# ADC_Buffering.net
KiCad netlist of a schematic drawn in Altium Designer
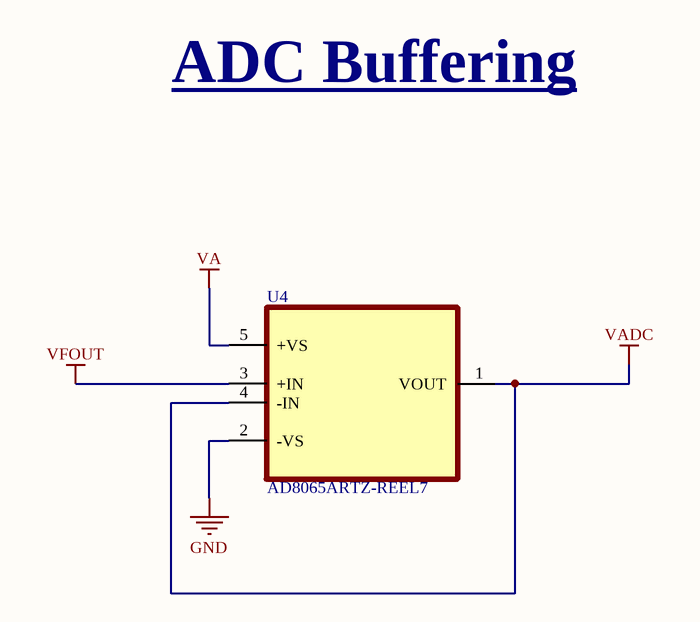
[diagram p0: ADC Buffering.SchDoc]

(export (version "E")
  (design (tool "Eeschema 10.0.6"))
  (components
    (comp (ref "U4")
      (value "AD8065ARTZ-REEL7")
      (footprint "SOT95P290X145-5N")
      (description "Voltage Feedback Amplifier 1 Circuit Rail-to-Rail SOT-23-5")
      (fields (field (name "MF") "Analog Devices"))
      (libsource (lib "AD8065ARTZ-REEL7") (part "AD8065ARTZ-REEL7"))
    )
  )
  (nets
    (net (code "1") (name "GND") (class "Default")
      (node (ref "U4") (pin "2") (pinfunction "-VS_2") (pintype "power_in"))
    )
    (net (code "2") (name "VA") (class "Default")
      (node (ref "U4") (pin "5") (pinfunction "+VS_5") (pintype "power_in"))
    )
    (net (code "3") (name "VADC") (class "Default")
      (node (ref "U4") (pin "1") (pinfunction "VOUT_1") (pintype "passive"))
      (node (ref "U4") (pin "4") (pinfunction "-IN_4") (pintype "passive"))
    )
    (net (code "4") (name "VFOUT") (class "Default")
      (node (ref "U4") (pin "3") (pinfunction "+IN_3") (pintype "passive"))
    )
  )
)
